# melzi.net
KiCad netlist of a schematic drawn in EAGLE
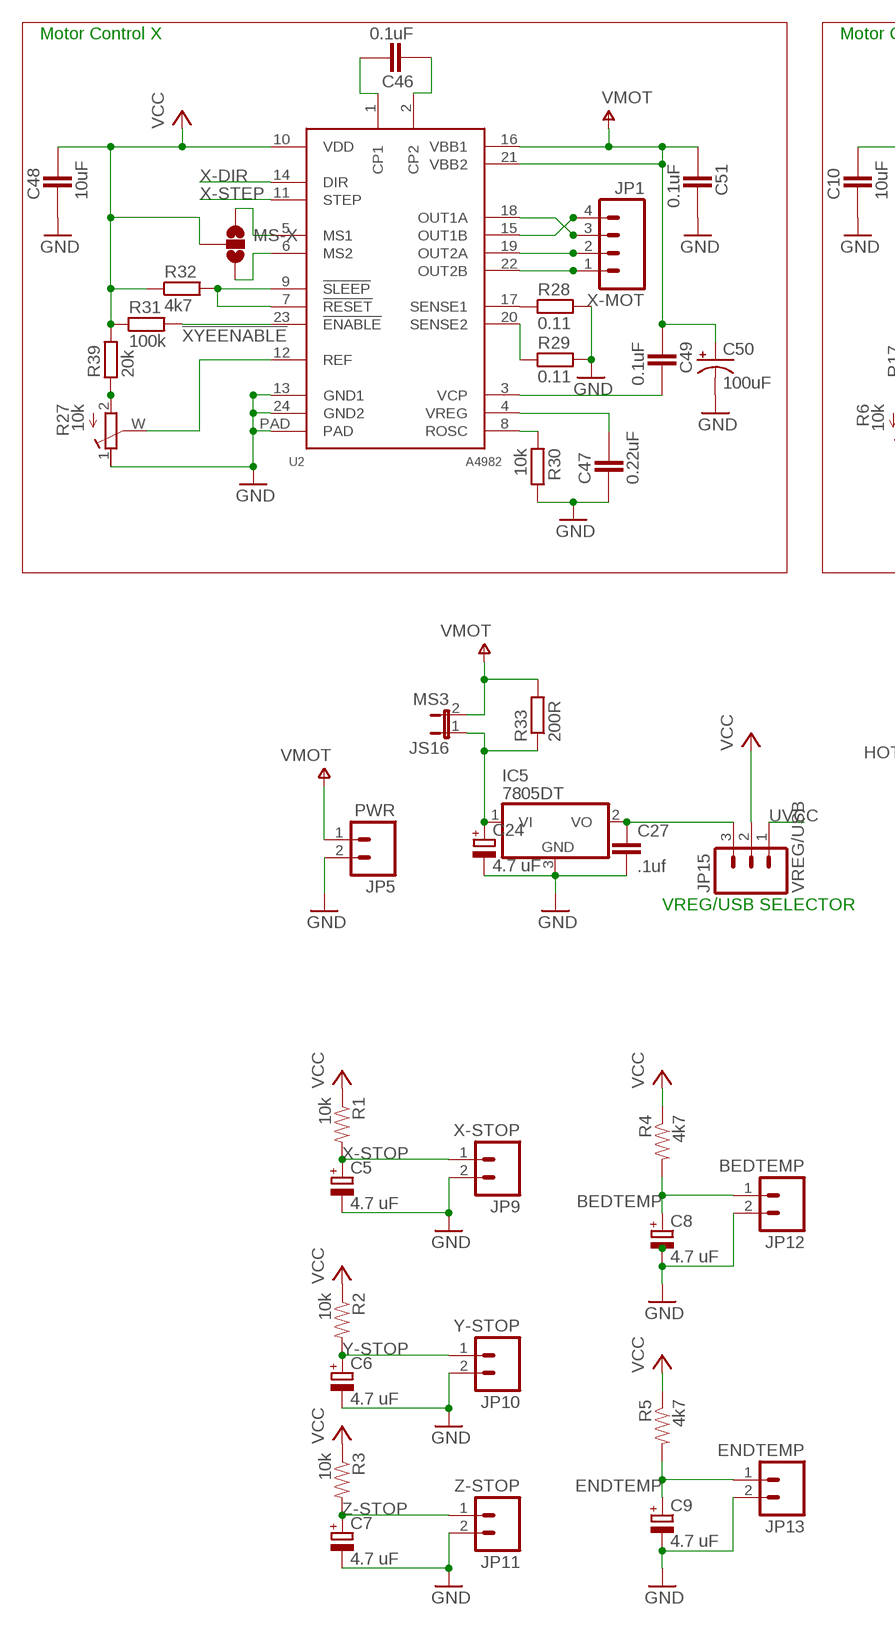
[diagram p0: schematic, sheet 1, part 1 of 2]
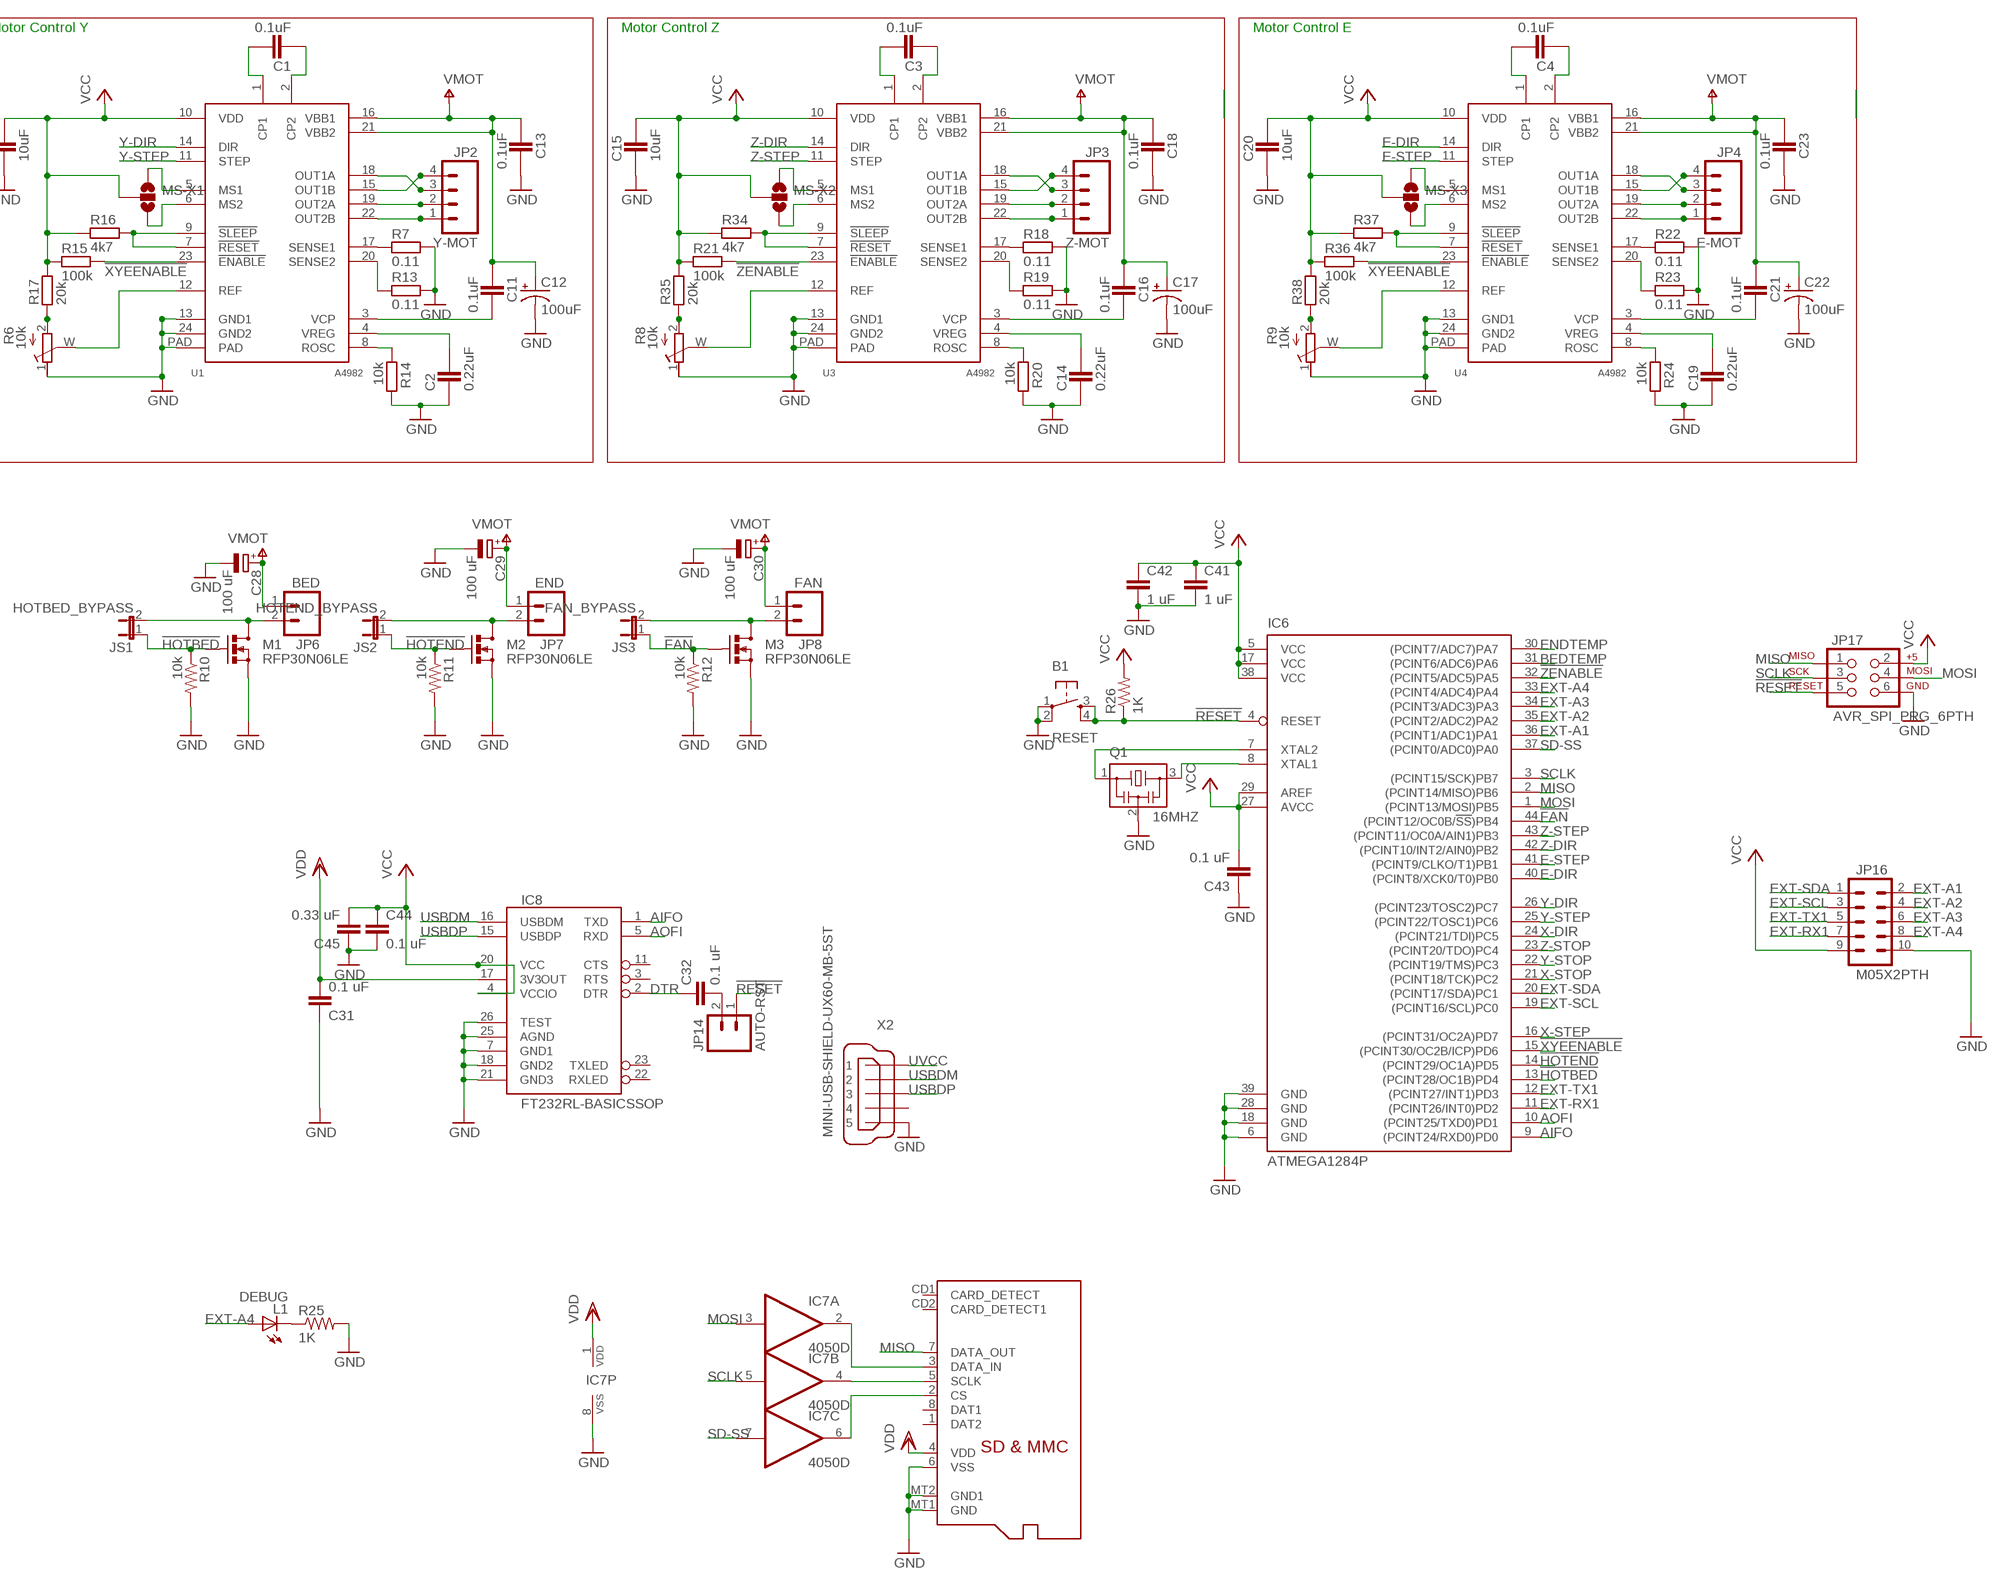
[diagram p1: schematic, sheet 1, part 2 of 2]

(export (version "E")
  (design (tool "Eeschema 10.0.6"))
  (components
    (comp (ref "B1")
      (value "RESET")
      (footprint "eagle-import:TACTILE_SWITCH_SMD")
      (libsource (lib "eagle-import") (part "TAC_SWITCHSMD"))
    )
    (comp (ref "C1")
      (value "0.1uF")
      (footprint "eagle-import:CAPC2012X145AN")
      (libsource (lib "eagle-import") (part "CAPACITOR_0805"))
    )
    (comp (ref "C2")
      (value "0.22uF")
      (footprint "eagle-import:CAPC2012X145AN")
      (libsource (lib "eagle-import") (part "CAPACITOR_0805"))
    )
    (comp (ref "C3")
      (value "0.1uF")
      (footprint "eagle-import:CAPC2012X145AN")
      (libsource (lib "eagle-import") (part "CAPACITOR_0805"))
    )
    (comp (ref "C4")
      (value "0.1uF")
      (footprint "eagle-import:CAPC2012X145AN")
      (libsource (lib "eagle-import") (part "CAPACITOR_0805"))
    )
    (comp (ref "C5")
      (value "4.7 uF")
      (footprint "eagle-import:SMC_C")
      (libsource (lib "eagle-import") (part "CPOL-EUSMCC"))
    )
    (comp (ref "C6")
      (value "4.7 uF")
      (footprint "eagle-import:SMC_C")
      (libsource (lib "eagle-import") (part "CPOL-EUSMCC"))
    )
    (comp (ref "C7")
      (value "4.7 uF")
      (footprint "eagle-import:SMC_C")
      (libsource (lib "eagle-import") (part "CPOL-EUSMCC"))
    )
    (comp (ref "C8")
      (value "4.7 uF")
      (footprint "eagle-import:SMC_C")
      (libsource (lib "eagle-import") (part "CPOL-EUSMCC"))
    )
    (comp (ref "C9")
      (value "4.7 uF")
      (footprint "eagle-import:SMC_C")
      (libsource (lib "eagle-import") (part "CPOL-EUSMCC"))
    )
    (comp (ref "C10")
      (value "10uF")
      (footprint "eagle-import:CAPC2012X145AN")
      (libsource (lib "eagle-import") (part "CAPACITOR_0805"))
    )
    (comp (ref "C11")
      (value "0.1uF")
      (footprint "eagle-import:CAPC2012X145AN")
      (libsource (lib "eagle-import") (part "CAPACITOR_0805"))
    )
    (comp (ref "C12")
      (value "100uF")
      (footprint "eagle-import:PANASONIC_D")
      (libsource (lib "eagle-import") (part "CPOL-USD"))
    )
    (comp (ref "C13")
      (value "0.1uF")
      (footprint "eagle-import:CAPC2012X145AN")
      (libsource (lib "eagle-import") (part "CAPACITOR_0805"))
    )
    (comp (ref "C14")
      (value "0.22uF")
      (footprint "eagle-import:CAPC2012X145AN")
      (libsource (lib "eagle-import") (part "CAPACITOR_0805"))
    )
    (comp (ref "C15")
      (value "10uF")
      (footprint "eagle-import:CAPC2012X145AN")
      (libsource (lib "eagle-import") (part "CAPACITOR_0805"))
    )
    (comp (ref "C16")
      (value "0.1uF")
      (footprint "eagle-import:CAPC2012X145AN")
      (libsource (lib "eagle-import") (part "CAPACITOR_0805"))
    )
    (comp (ref "C17")
      (value "100uF")
      (footprint "eagle-import:PANASONIC_D")
      (libsource (lib "eagle-import") (part "CPOL-USD"))
    )
    (comp (ref "C18")
      (value "0.1uF")
      (footprint "eagle-import:CAPC2012X145AN")
      (libsource (lib "eagle-import") (part "CAPACITOR_0805"))
    )
    (comp (ref "C19")
      (value "0.22uF")
      (footprint "eagle-import:CAPC2012X145AN")
      (libsource (lib "eagle-import") (part "CAPACITOR_0805"))
    )
    (comp (ref "C20")
      (value "10uF")
      (footprint "eagle-import:CAPC2012X145AN")
      (libsource (lib "eagle-import") (part "CAPACITOR_0805"))
    )
    (comp (ref "C21")
      (value "0.1uF")
      (footprint "eagle-import:CAPC2012X145AN")
      (libsource (lib "eagle-import") (part "CAPACITOR_0805"))
    )
    (comp (ref "C22")
      (value "100uF")
      (footprint "eagle-import:PANASONIC_D")
      (libsource (lib "eagle-import") (part "CPOL-USD"))
    )
    (comp (ref "C23")
      (value "0.1uF")
      (footprint "eagle-import:CAPC2012X145AN")
      (libsource (lib "eagle-import") (part "CAPACITOR_0805"))
    )
    (comp (ref "C24")
      (value "4.7 uF")
      (footprint "eagle-import:SMC_C")
      (libsource (lib "eagle-import") (part "CPOL-EUSMCC"))
    )
    (comp (ref "C27")
      (value ".1uf")
      (footprint "eagle-import:0805")
      (libsource (lib "eagle-import") (part "CAP0805"))
    )
    (comp (ref "C28")
      (value "100 uF")
      (footprint "eagle-import:UD-6,3X7,7_NICHICON")
      (libsource (lib "eagle-import") (part "CPOL-EUUD-6,3X7,7"))
    )
    (comp (ref "C29")
      (value "100 uF")
      (footprint "eagle-import:UD-6,3X7,7_NICHICON")
      (libsource (lib "eagle-import") (part "CPOL-EUUD-6,3X7,7"))
    )
    (comp (ref "C30")
      (value "100 uF")
      (footprint "eagle-import:UD-6,3X7,7_NICHICON")
      (libsource (lib "eagle-import") (part "CPOL-EUUD-6,3X7,7"))
    )
    (comp (ref "C31")
      (value "0.1 uF")
      (footprint "eagle-import:C1206")
      (libsource (lib "eagle-import") (part "C-EUC1206"))
    )
    (comp (ref "C32")
      (value "0.1 uF")
      (footprint "eagle-import:C1206")
      (libsource (lib "eagle-import") (part "C-EUC1206"))
    )
    (comp (ref "C41")
      (value "1 uF")
      (footprint "eagle-import:C1206")
      (libsource (lib "eagle-import") (part "C-EUC1206"))
    )
    (comp (ref "C42")
      (value "1 uF")
      (footprint "eagle-import:C1206")
      (libsource (lib "eagle-import") (part "C-EUC1206"))
    )
    (comp (ref "C43")
      (value "0.1 uF")
      (footprint "eagle-import:C1206")
      (libsource (lib "eagle-import") (part "C-EUC1206"))
    )
    (comp (ref "C44")
      (value "0.1 uF")
      (footprint "eagle-import:C1206")
      (libsource (lib "eagle-import") (part "C-EUC1206"))
    )
    (comp (ref "C45")
      (value "0.33 uF")
      (footprint "eagle-import:C1206")
      (libsource (lib "eagle-import") (part "C-EUC1206"))
    )
    (comp (ref "C46")
      (value "0.1uF")
      (footprint "eagle-import:CAPC2012X145AN")
      (libsource (lib "eagle-import") (part "CAPACITOR_0805"))
    )
    (comp (ref "C47")
      (value "0.22uF")
      (footprint "eagle-import:CAPC2012X145AN")
      (libsource (lib "eagle-import") (part "CAPACITOR_0805"))
    )
    (comp (ref "C48")
      (value "10uF")
      (footprint "eagle-import:CAPC2012X145AN")
      (libsource (lib "eagle-import") (part "CAPACITOR_0805"))
    )
    (comp (ref "C49")
      (value "0.1uF")
      (footprint "eagle-import:CAPC2012X145AN")
      (libsource (lib "eagle-import") (part "CAPACITOR_0805"))
    )
    (comp (ref "C50")
      (value "100uF")
      (footprint "eagle-import:PANASONIC_D")
      (libsource (lib "eagle-import") (part "CPOL-USD"))
    )
    (comp (ref "C51")
      (value "0.1uF")
      (footprint "eagle-import:CAPC2012X145AN")
      (libsource (lib "eagle-import") (part "CAPACITOR_0805"))
    )
    (comp (ref "IC5")
      (value "7805DT")
      (footprint "eagle-import:TO252")
      (libsource (lib "eagle-import") (part "78DT05"))
    )
    (comp (ref "IC6")
      (value "ATMEGA1284P")
      (footprint "eagle-import:TQFP44")
      (fields (field (name "MPN") "ATMEGA644PV-10AU"))
      (libsource (lib "eagle-import") (part "ATMEGA644A"))
    )
    (comp (ref "IC7")
      (value "4050D")
      (footprint "eagle-import:SO16")
      (libsource (lib "eagle-import") (part "4050D"))
    )
    (comp (ref "IC8")
      (value "FT232RL-BASICSSOP")
      (footprint "eagle-import:SSOP28DB")
      (libsource (lib "eagle-import") (part "FT232RL-BASICSSOP"))
    )
    (comp (ref "JP1")
      (value "X-MOT")
      (footprint "eagle-import:SCREWTERMINAL-3.5MM-4")
      (libsource (lib "eagle-import") (part "M04SCREW"))
    )
    (comp (ref "JP2")
      (value "Y-MOT")
      (footprint "eagle-import:SCREWTERMINAL-3.5MM-4")
      (libsource (lib "eagle-import") (part "M04SCREW"))
    )
    (comp (ref "JP3")
      (value "Z-MOT")
      (footprint "eagle-import:SCREWTERMINAL-3.5MM-4")
      (libsource (lib "eagle-import") (part "M04SCREW"))
    )
    (comp (ref "JP4")
      (value "E-MOT")
      (footprint "eagle-import:SCREWTERMINAL-3.5MM-4")
      (libsource (lib "eagle-import") (part "M04SCREW"))
    )
    (comp (ref "JP5")
      (value "PWR")
      (footprint "eagle-import:SCREWTERMINAL-5MM-2")
      (libsource (lib "eagle-import") (part "M025MM"))
    )
    (comp (ref "JP6")
      (value "BED")
      (footprint "eagle-import:SCREWTERMINAL-5MM-2")
      (libsource (lib "eagle-import") (part "M025MM"))
    )
    (comp (ref "JP7")
      (value "END")
      (footprint "eagle-import:SCREWTERMINAL-5MM-2")
      (libsource (lib "eagle-import") (part "M025MM"))
    )
    (comp (ref "JP8")
      (value "FAN")
      (footprint "eagle-import:SCREWTERMINAL-5MM-2")
      (libsource (lib "eagle-import") (part "M025MM"))
    )
    (comp (ref "JP9")
      (value "X-STOP")
      (footprint "eagle-import:SCREWTERMINAL-3.5MM-2")
      (libsource (lib "eagle-import") (part "M023.5MM"))
    )
    (comp (ref "JP10")
      (value "Y-STOP")
      (footprint "eagle-import:SCREWTERMINAL-3.5MM-2")
      (libsource (lib "eagle-import") (part "M023.5MM"))
    )
    (comp (ref "JP11")
      (value "Z-STOP")
      (footprint "eagle-import:SCREWTERMINAL-3.5MM-2")
      (libsource (lib "eagle-import") (part "M023.5MM"))
    )
    (comp (ref "JP12")
      (value "BEDTEMP")
      (footprint "eagle-import:SCREWTERMINAL-3.5MM-2")
      (libsource (lib "eagle-import") (part "M023.5MM"))
    )
    (comp (ref "JP13")
      (value "ENDTEMP")
      (footprint "eagle-import:SCREWTERMINAL-3.5MM-2")
      (libsource (lib "eagle-import") (part "M023.5MM"))
    )
    (comp (ref "JP14")
      (value "AUTO-RST")
      (footprint "eagle-import:1X02")
      (libsource (lib "eagle-import") (part "M02PTH"))
    )
    (comp (ref "JP15")
      (value "VREG/USB")
      (footprint "eagle-import:1X03")
      (libsource (lib "eagle-import") (part "M03PTH"))
    )
    (comp (ref "JP16")
      (value "M05X2PTH")
      (footprint "eagle-import:AVR_ICSP")
      (libsource (lib "eagle-import") (part "M05X2PTH"))
    )
    (comp (ref "JP17")
      (value "AVR_SPI_PRG_6PTH")
      (footprint "eagle-import:2X3")
      (libsource (lib "eagle-import") (part "AVR_SPI_PRG_6PTH"))
    )
    (comp (ref "JS1")
      (value "HOTBED_BYPASS")
      (footprint "eagle-import:SJ_2S-NO")
      (libsource (lib "eagle-import") (part "JUMPER-2SMD-NO"))
    )
    (comp (ref "JS2")
      (value "HOTEND_BYPASS")
      (footprint "eagle-import:SJ_2S-NO")
      (libsource (lib "eagle-import") (part "JUMPER-2SMD-NO"))
    )
    (comp (ref "JS3")
      (value "FAN_BYPASS")
      (footprint "eagle-import:SJ_2S-NO")
      (libsource (lib "eagle-import") (part "JUMPER-2SMD-NO"))
    )
    (comp (ref "JS16")
      (value "MS3")
      (footprint "eagle-import:SJ_2S")
      (libsource (lib "eagle-import") (part "JUMPER-2SMD-NC"))
    )
    (comp (ref "L1")
      (value "DEBUG")
      (footprint "eagle-import:LED-1206")
      (libsource (lib "eagle-import") (part "LED1206"))
    )
    (comp (ref "M1")
      (value "RFP30N06LE")
      (footprint "eagle-import:DPAK")
      (libsource (lib "eagle-import") (part "MOSFET-NCHANNELFDD8580"))
    )
    (comp (ref "M2")
      (value "RFP30N06LE")
      (footprint "eagle-import:DPAK")
      (libsource (lib "eagle-import") (part "MOSFET-NCHANNELFDD8580"))
    )
    (comp (ref "M3")
      (value "RFP30N06LE")
      (footprint "eagle-import:DPAK")
      (libsource (lib "eagle-import") (part "MOSFET-NCHANNELFDD8580"))
    )
    (comp (ref "MS-X")
      (value "SOLDERJUMPER_2WAYCONNECTED")
      (footprint "eagle-import:SJ_3_CONNECTED")
      (libsource (lib "eagle-import") (part "SOLDERJUMPER_2WAYCONNECTED"))
    )
    (comp (ref "MS-X1")
      (value "SOLDERJUMPER_2WAYCONNECTED")
      (footprint "eagle-import:SJ_3_CONNECTED")
      (libsource (lib "eagle-import") (part "SOLDERJUMPER_2WAYCONNECTED"))
    )
    (comp (ref "MS-X2")
      (value "SOLDERJUMPER_2WAYCONNECTED")
      (footprint "eagle-import:SJ_3_CONNECTED")
      (libsource (lib "eagle-import") (part "SOLDERJUMPER_2WAYCONNECTED"))
    )
    (comp (ref "MS-X3")
      (value "SOLDERJUMPER_2WAYCONNECTED")
      (footprint "eagle-import:SJ_3_CONNECTED")
      (libsource (lib "eagle-import") (part "SOLDERJUMPER_2WAYCONNECTED"))
    )
    (comp (ref "Q1")
      (value "16MHZ")
      (footprint "eagle-import:CSTCR6M")
      (fields (field (name "MPN") "CSTCR6M00G53-R0"))
      (libsource (lib "eagle-import") (part "CSTCR6M00G53Z"))
    )
    (comp (ref "R1")
      (value "10k")
      (footprint "eagle-import:1206")
      (libsource (lib "eagle-import") (part "RESISTOR1206"))
    )
    (comp (ref "R2")
      (value "10k")
      (footprint "eagle-import:1206")
      (libsource (lib "eagle-import") (part "RESISTOR1206"))
    )
    (comp (ref "R3")
      (value "10k")
      (footprint "eagle-import:1206")
      (libsource (lib "eagle-import") (part "RESISTOR1206"))
    )
    (comp (ref "R4")
      (value "4k7")
      (footprint "eagle-import:1206")
      (libsource (lib "eagle-import") (part "RESISTOR1206"))
    )
    (comp (ref "R5")
      (value "4k7")
      (footprint "eagle-import:1206")
      (libsource (lib "eagle-import") (part "RESISTOR1206"))
    )
    (comp (ref "R6")
      (value "10k")
      (footprint "eagle-import:RTRIM-ST4ETB")
      (libsource (lib "eagle-import") (part "RTRIM-ST-4EA"))
    )
    (comp (ref "R7")
      (value "0.11")
      (footprint "eagle-import:RESC2012X70N")
      (libsource (lib "eagle-import") (part "RESISTOR_0805"))
    )
    (comp (ref "R8")
      (value "10k")
      (footprint "eagle-import:RTRIM-ST4ETB")
      (libsource (lib "eagle-import") (part "RTRIM-ST-4EA"))
    )
    (comp (ref "R9")
      (value "10k")
      (footprint "eagle-import:RTRIM-ST4ETB")
      (libsource (lib "eagle-import") (part "RTRIM-ST-4EA"))
    )
    (comp (ref "R10")
      (value "10k")
      (footprint "eagle-import:1206")
      (libsource (lib "eagle-import") (part "RESISTOR1206"))
    )
    (comp (ref "R11")
      (value "10k")
      (footprint "eagle-import:1206")
      (libsource (lib "eagle-import") (part "RESISTOR1206"))
    )
    (comp (ref "R12")
      (value "10k")
      (footprint "eagle-import:1206")
      (libsource (lib "eagle-import") (part "RESISTOR1206"))
    )
    (comp (ref "R13")
      (value "0.11")
      (footprint "eagle-import:RESC2012X70N")
      (libsource (lib "eagle-import") (part "RESISTOR_0805"))
    )
    (comp (ref "R14")
      (value "10k")
      (footprint "eagle-import:RESC2012X70N")
      (libsource (lib "eagle-import") (part "RESISTOR_0805"))
    )
    (comp (ref "R15")
      (value "100k")
      (footprint "eagle-import:RESC2012X70N")
      (libsource (lib "eagle-import") (part "RESISTOR_0805"))
    )
    (comp (ref "R16")
      (value "4k7")
      (footprint "eagle-import:RESC2012X70N")
      (libsource (lib "eagle-import") (part "RESISTOR_0805"))
    )
    (comp (ref "R17")
      (value "20k")
      (footprint "eagle-import:RESC2012X70N")
      (libsource (lib "eagle-import") (part "RESISTOR_0805"))
    )
    (comp (ref "R18")
      (value "0.11")
      (footprint "eagle-import:RESC2012X70N")
      (libsource (lib "eagle-import") (part "RESISTOR_0805"))
    )
    (comp (ref "R19")
      (value "0.11")
      (footprint "eagle-import:RESC2012X70N")
      (libsource (lib "eagle-import") (part "RESISTOR_0805"))
    )
    (comp (ref "R20")
      (value "10k")
      (footprint "eagle-import:RESC2012X70N")
      (libsource (lib "eagle-import") (part "RESISTOR_0805"))
    )
    (comp (ref "R21")
      (value "100k")
      (footprint "eagle-import:RESC2012X70N")
      (libsource (lib "eagle-import") (part "RESISTOR_0805"))
    )
    (comp (ref "R22")
      (value "0.11")
      (footprint "eagle-import:RESC2012X70N")
      (libsource (lib "eagle-import") (part "RESISTOR_0805"))
    )
    (comp (ref "R23")
      (value "0.11")
      (footprint "eagle-import:RESC2012X70N")
      (libsource (lib "eagle-import") (part "RESISTOR_0805"))
    )
    (comp (ref "R24")
      (value "10k")
      (footprint "eagle-import:RESC2012X70N")
      (libsource (lib "eagle-import") (part "RESISTOR_0805"))
    )
    (comp (ref "R25")
      (value "1K")
      (footprint "eagle-import:1206")
      (libsource (lib "eagle-import") (part "RESISTOR1206"))
    )
    (comp (ref "R26")
      (value "1K")
      (footprint "eagle-import:1206")
      (libsource (lib "eagle-import") (part "RESISTOR1206"))
    )
    (comp (ref "R27")
      (value "10k")
      (footprint "eagle-import:RTRIM-ST4ETB")
      (libsource (lib "eagle-import") (part "RTRIM-ST-4EA"))
    )
    (comp (ref "R28")
      (value "0.11")
      (footprint "eagle-import:RESC2012X70N")
      (libsource (lib "eagle-import") (part "RESISTOR_0805"))
    )
    (comp (ref "R29")
      (value "0.11")
      (footprint "eagle-import:RESC2012X70N")
      (libsource (lib "eagle-import") (part "RESISTOR_0805"))
    )
    (comp (ref "R30")
      (value "10k")
      (footprint "eagle-import:RESC2012X70N")
      (libsource (lib "eagle-import") (part "RESISTOR_0805"))
    )
    (comp (ref "R31")
      (value "100k")
      (footprint "eagle-import:RESC2012X70N")
      (libsource (lib "eagle-import") (part "RESISTOR_0805"))
    )
    (comp (ref "R32")
      (value "4k7")
      (footprint "eagle-import:RESC2012X70N")
      (libsource (lib "eagle-import") (part "RESISTOR_0805"))
    )
    (comp (ref "R33")
      (value "200R")
      (footprint "eagle-import:0309V")
      (libsource (lib "eagle-import") (part "R-EU_0309/V"))
    )
    (comp (ref "R34")
      (value "4k7")
      (footprint "eagle-import:RESC2012X70N")
      (libsource (lib "eagle-import") (part "RESISTOR_0805"))
    )
    (comp (ref "R35")
      (value "20k")
      (footprint "eagle-import:RESC2012X70N")
      (libsource (lib "eagle-import") (part "RESISTOR_0805"))
    )
    (comp (ref "R36")
      (value "100k")
      (footprint "eagle-import:RESC2012X70N")
      (libsource (lib "eagle-import") (part "RESISTOR_0805"))
    )
    (comp (ref "R37")
      (value "4k7")
      (footprint "eagle-import:RESC2012X70N")
      (libsource (lib "eagle-import") (part "RESISTOR_0805"))
    )
    (comp (ref "R38")
      (value "20k")
      (footprint "eagle-import:RESC2012X70N")
      (libsource (lib "eagle-import") (part "RESISTOR_0805"))
    )
    (comp (ref "R39")
      (value "20k")
      (footprint "eagle-import:RESC2012X70N")
      (libsource (lib "eagle-import") (part "RESISTOR_0805"))
    )
    (comp (ref "U1")
      (value "A4982")
      (footprint "eagle-import:TSSOP-24")
      (libsource (lib "eagle-import") (part "A4982"))
    )
    (comp (ref "U2")
      (value "A4982")
      (footprint "eagle-import:TSSOP-24")
      (libsource (lib "eagle-import") (part "A4982"))
    )
    (comp (ref "U3")
      (value "A4982")
      (footprint "eagle-import:TSSOP-24")
      (libsource (lib "eagle-import") (part "A4982"))
    )
    (comp (ref "U4")
      (value "A4982")
      (footprint "eagle-import:TSSOP-24")
      (libsource (lib "eagle-import") (part "A4982"))
    )
    (comp (ref "X1")
      (value "MICROSD")
      (footprint "eagle-import:MICROSD")
      (libsource (lib "eagle-import") (part "MICROSD"))
    )
    (comp (ref "X2")
      (value "MINI-USB-SHIELD-UX60-MB-5ST")
      (footprint "eagle-import:UX60-MB-5ST")
      (libsource (lib "eagle-import") (part "MINI-USB-SHIELD-UX60-MB-5ST"))
    )
  )
  (nets
    (net (code "1") (name "/AIFO") (class "Default")
      (node (ref "IC6") (pin "9") (pinfunction "(PCINT24/RXD0)PD0_9") (pintype "bidirectional"))
      (node (ref "IC8") (pin "1") (pinfunction "TXD_1") (pintype "output"))
    )
    (net (code "2") (name "/AOFI") (class "Default")
      (node (ref "IC6") (pin "10") (pinfunction "(PCINT25/TXD0)PD1_10") (pintype "bidirectional"))
      (node (ref "IC8") (pin "5") (pinfunction "RXD_5") (pintype "input"))
    )
    (net (code "3") (name "/BEDTEMP") (class "Default")
      (node (ref "C8") (pin "+") (pinfunction "+_+") (pintype "passive"))
      (node (ref "IC6") (pin "31") (pinfunction "(PCINT6/ADC6)PA6_31") (pintype "bidirectional"))
      (node (ref "JP12") (pin "1") (pinfunction "1_1") (pintype "passive"))
      (node (ref "R4") (pin "2") (pinfunction "2_2") (pintype "passive"))
    )
    (net (code "4") (name "/DTR") (class "Default")
      (node (ref "C32") (pin "1") (pinfunction "1_1") (pintype "passive"))
      (node (ref "IC8") (pin "2") (pinfunction "DTR_2") (pintype "bidirectional"))
    )
    (net (code "5") (name "/E-DIR") (class "Default")
      (node (ref "IC6") (pin "40") (pinfunction "(PCINT8/XCK0/T0)PB0_40") (pintype "bidirectional"))
      (node (ref "U4") (pin "14") (pinfunction "DIR_14") (pintype "input"))
    )
    (net (code "6") (name "/E-STEP") (class "Default")
      (node (ref "IC6") (pin "41") (pinfunction "(PCINT9/CLKO/T1)PB1_41") (pintype "bidirectional"))
      (node (ref "U4") (pin "11") (pinfunction "STEP_11") (pintype "input"))
    )
    (net (code "7") (name "/ENDTEMP") (class "Default")
      (node (ref "C9") (pin "+") (pinfunction "+_+") (pintype "passive"))
      (node (ref "IC6") (pin "30") (pinfunction "(PCINT7/ADC7)PA7_30") (pintype "bidirectional"))
      (node (ref "JP13") (pin "1") (pinfunction "1_1") (pintype "passive"))
      (node (ref "R5") (pin "2") (pinfunction "2_2") (pintype "passive"))
    )
    (net (code "8") (name "/EXT-A1") (class "Default")
      (node (ref "IC6") (pin "36") (pinfunction "(PCINT1/ADC1)PA1_36") (pintype "bidirectional"))
      (node (ref "JP16") (pin "2") (pinfunction "2_2") (pintype "passive"))
    )
    (net (code "9") (name "/EXT-A2") (class "Default")
      (node (ref "IC6") (pin "35") (pinfunction "(PCINT2/ADC2)PA2_35") (pintype "bidirectional"))
      (node (ref "JP16") (pin "4") (pinfunction "4_4") (pintype "passive"))
    )
    (net (code "10") (name "/EXT-A3") (class "Default")
      (node (ref "IC6") (pin "34") (pinfunction "(PCINT3/ADC3)PA3_34") (pintype "bidirectional"))
      (node (ref "JP16") (pin "6") (pinfunction "6_6") (pintype "passive"))
    )
    (net (code "11") (name "/EXT-A4") (class "Default")
      (node (ref "IC6") (pin "33") (pinfunction "(PCINT4/ADC4)PA4_33") (pintype "bidirectional"))
      (node (ref "JP16") (pin "8") (pinfunction "8_8") (pintype "passive"))
      (node (ref "L1") (pin "A") (pinfunction "A_A") (pintype "passive"))
    )
    (net (code "12") (name "/EXT-RX1") (class "Default")
      (node (ref "IC6") (pin "11") (pinfunction "(PCINT26/INT0)PD2_11") (pintype "bidirectional"))
      (node (ref "JP16") (pin "7") (pinfunction "7_7") (pintype "passive"))
    )
    (net (code "13") (name "/EXT-SCL") (class "Default")
      (node (ref "IC6") (pin "19") (pinfunction "(PCINT16/SCL)PC0_19") (pintype "output"))
      (node (ref "JP16") (pin "3") (pinfunction "3_3") (pintype "passive"))
    )
    (net (code "14") (name "/EXT-SDA") (class "Default")
      (node (ref "IC6") (pin "20") (pinfunction "(PCINT17/SDA)PC1_20") (pintype "output"))
      (node (ref "JP16") (pin "1") (pinfunction "1_1") (pintype "passive"))
    )
    (net (code "15") (name "/EXT-TX1") (class "Default")
      (node (ref "IC6") (pin "12") (pinfunction "(PCINT27/INT1)PD3_12") (pintype "bidirectional"))
      (node (ref "JP16") (pin "5") (pinfunction "5_5") (pintype "passive"))
    )
    (net (code "16") (name "/MISO") (class "Default")
      (node (ref "IC6") (pin "2") (pinfunction "(PCINT14/MISO)PB6_2") (pintype "bidirectional"))
      (node (ref "JP17") (pin "1") (pinfunction "1_1") (pintype "passive"))
      (node (ref "X1") (pin "7") (pinfunction "DATA_OUT_7") (pintype "output"))
    )
    (net (code "17") (name "/MOSI") (class "Default")
      (node (ref "IC6") (pin "1") (pinfunction "(PCINT13/MOSI)PB5_1") (pintype "bidirectional"))
      (node (ref "IC7") (pin "3") (pinfunction "I_3") (pintype "input"))
      (node (ref "JP17") (pin "4") (pinfunction "4_4") (pintype "passive"))
    )
    (net (code "18") (name "/SCLK") (class "Default")
      (node (ref "IC6") (pin "3") (pinfunction "(PCINT15/SCK)PB7_3") (pintype "bidirectional"))
      (node (ref "IC7") (pin "5") (pinfunction "I_5") (pintype "input"))
      (node (ref "JP17") (pin "3") (pinfunction "3_3") (pintype "passive"))
    )
    (net (code "19") (name "/SD-SS") (class "Default")
      (node (ref "IC6") (pin "37") (pinfunction "(PCINT0/ADC0)PA0_37") (pintype "bidirectional"))
      (node (ref "IC7") (pin "7") (pinfunction "I_7") (pintype "input"))
    )
    (net (code "20") (name "/USBDM") (class "Default")
      (node (ref "IC8") (pin "16") (pinfunction "USBDM_16") (pintype "bidirectional"))
      (node (ref "X2") (pin "2") (pinfunction "2_2") (pintype "input"))
    )
    (net (code "21") (name "/USBDP") (class "Default")
      (node (ref "IC8") (pin "15") (pinfunction "USBDP_15") (pintype "bidirectional"))
      (node (ref "X2") (pin "3") (pinfunction "3_3") (pintype "input"))
    )
    (net (code "22") (name "/UVCC") (class "Default")
      (node (ref "JP15") (pin "1") (pinfunction "1_1") (pintype "passive"))
      (node (ref "X2") (pin "1") (pinfunction "1_1") (pintype "input"))
    )
    (net (code "23") (name "/X-DIR") (class "Default")
      (node (ref "IC6") (pin "24") (pinfunction "(PCINT21/TDI)PC5_24") (pintype "output"))
      (node (ref "U2") (pin "14") (pinfunction "DIR_14") (pintype "input"))
    )
    (net (code "24") (name "/X-STEP") (class "Default")
      (node (ref "IC6") (pin "16") (pinfunction "(PCINT31/OC2A)PD7_16") (pintype "bidirectional"))
      (node (ref "U2") (pin "11") (pinfunction "STEP_11") (pintype "input"))
    )
    (net (code "25") (name "/X-STOP") (class "Default")
      (node (ref "C5") (pin "+") (pinfunction "+_+") (pintype "passive"))
      (node (ref "IC6") (pin "21") (pinfunction "(PCINT18/TCK)PC2_21") (pintype "output"))
      (node (ref "JP9") (pin "1") (pinfunction "1_1") (pintype "passive"))
      (node (ref "R1") (pin "2") (pinfunction "2_2") (pintype "passive"))
    )
    (net (code "26") (name "/Y-DIR") (class "Default")
      (node (ref "IC6") (pin "26") (pinfunction "(PCINT23/TOSC2)PC7_26") (pintype "output"))
      (node (ref "U1") (pin "14") (pinfunction "DIR_14") (pintype "input"))
    )
    (net (code "27") (name "/Y-STEP") (class "Default")
      (node (ref "IC6") (pin "25") (pinfunction "(PCINT22/TOSC1)PC6_25") (pintype "output"))
      (node (ref "U1") (pin "11") (pinfunction "STEP_11") (pintype "input"))
    )
    (net (code "28") (name "/Y-STOP") (class "Default")
      (node (ref "C6") (pin "+") (pinfunction "+_+") (pintype "passive"))
      (node (ref "IC6") (pin "22") (pinfunction "(PCINT19/TMS)PC3_22") (pintype "output"))
      (node (ref "JP10") (pin "1") (pinfunction "1_1") (pintype "passive"))
      (node (ref "R2") (pin "2") (pinfunction "2_2") (pintype "passive"))
    )
    (net (code "29") (name "/Z-DIR") (class "Default")
      (node (ref "IC6") (pin "42") (pinfunction "(PCINT10/INT2/AIN0)PB2_42") (pintype "bidirectional"))
      (node (ref "U3") (pin "14") (pinfunction "DIR_14") (pintype "input"))
    )
    (net (code "30") (name "/Z-STEP") (class "Default")
      (node (ref "IC6") (pin "43") (pinfunction "(PCINT11/OC0A/AIN1)PB3_43") (pintype "bidirectional"))
      (node (ref "U3") (pin "11") (pinfunction "STEP_11") (pintype "input"))
    )
    (net (code "31") (name "/Z-STOP") (class "Default")
      (node (ref "C7") (pin "+") (pinfunction "+_+") (pintype "passive"))
      (node (ref "IC6") (pin "23") (pinfunction "(PCINT20/TDO)PC4_23") (pintype "output"))
      (node (ref "JP11") (pin "1") (pinfunction "1_1") (pintype "passive"))
      (node (ref "R3") (pin "2") (pinfunction "2_2") (pintype "passive"))
    )
    (net (code "32") (name "/~{FAN}") (class "Default")
      (node (ref "IC6") (pin "44") (pinfunction "(PCINT12/OC0B/~{SS})PB4_44") (pintype "bidirectional"))
      (node (ref "JS3") (pin "1") (pinfunction "1_1") (pintype "passive"))
      (node (ref "M3") (pin "1") (pinfunction "G_1") (pintype "passive"))
      (node (ref "R12") (pin "1") (pinfunction "1_1") (pintype "passive"))
    )
    (net (code "33") (name "/~{HOTBED}") (class "Default")
      (node (ref "IC6") (pin "13") (pinfunction "(PCINT28/OC1B)PD4_13") (pintype "bidirectional"))
      (node (ref "JS1") (pin "1") (pinfunction "1_1") (pintype "passive"))
      (node (ref "M1") (pin "1") (pinfunction "G_1") (pintype "passive"))
      (node (ref "R10") (pin "1") (pinfunction "1_1") (pintype "passive"))
    )
    (net (code "34") (name "/~{HOTEND}") (class "Default")
      (node (ref "IC6") (pin "14") (pinfunction "(PCINT29/OC1A)PD5_14") (pintype "bidirectional"))
      (node (ref "JS2") (pin "1") (pinfunction "1_1") (pintype "passive"))
      (node (ref "M2") (pin "1") (pinfunction "G_1") (pintype "passive"))
      (node (ref "R11") (pin "1") (pinfunction "1_1") (pintype "passive"))
    )
    (net (code "35") (name "/~{RESET}") (class "Default")
      (node (ref "B1") (pin "3") (pinfunction "3_3") (pintype "passive"))
      (node (ref "B1") (pin "4") (pinfunction "4_4") (pintype "passive"))
      (node (ref "IC6") (pin "4") (pinfunction "RESET_4") (pintype "input"))
      (node (ref "JP14") (pin "1") (pinfunction "1_1") (pintype "passive"))
      (node (ref "JP17") (pin "5") (pinfunction "5_5") (pintype "passive"))
      (node (ref "R26") (pin "1") (pinfunction "1_1") (pintype "passive"))
    )
    (net (code "36") (name "/~{XYEENABLE}") (class "Default")
      (node (ref "IC6") (pin "15") (pinfunction "(PCINT30/OC2B/ICP)PD6_15") (pintype "bidirectional"))
      (node (ref "R15") (pin "2") (pinfunction "2_2") (pintype "passive"))
      (node (ref "R31") (pin "2") (pinfunction "2_2") (pintype "passive"))
      (node (ref "R36") (pin "2") (pinfunction "2_2") (pintype "passive"))
      (node (ref "U1") (pin "23") (pinfunction "~{ENABLE}_23") (pintype "input"))
      (node (ref "U2") (pin "23") (pinfunction "~{ENABLE}_23") (pintype "input"))
      (node (ref "U4") (pin "23") (pinfunction "~{ENABLE}_23") (pintype "input"))
    )
    (net (code "37") (name "/~{ZENABLE}") (class "Default")
      (node (ref "IC6") (pin "32") (pinfunction "(PCINT5/ADC5)PA5_32") (pintype "bidirectional"))
      (node (ref "R21") (pin "2") (pinfunction "2_2") (pintype "passive"))
      (node (ref "U3") (pin "23") (pinfunction "~{ENABLE}_23") (pintype "input"))
    )
    (net (code "38") (name "GND") (class "Default")
      (node (ref "B1") (pin "1") (pinfunction "1_1") (pintype "passive"))
      (node (ref "B1") (pin "2") (pinfunction "2_2") (pintype "passive"))
      (node (ref "C10") (pin "1") (pinfunction "1_1") (pintype "passive"))
      (node (ref "C12") (pin "-") (pinfunction "-_-") (pintype "passive"))
      (node (ref "C13") (pin "2") (pinfunction "2_2") (pintype "passive"))
      (node (ref "C14") (pin "1") (pinfunction "1_1") (pintype "passive"))
      (node (ref "C15") (pin "1") (pinfunction "1_1") (pintype "passive"))
      (node (ref "C17") (pin "-") (pinfunction "-_-") (pintype "passive"))
      (node (ref "C18") (pin "2") (pinfunction "2_2") (pintype "passive"))
      (node (ref "C19") (pin "1") (pinfunction "1_1") (pintype "passive"))
      (node (ref "C2") (pin "1") (pinfunction "1_1") (pintype "passive"))
      (node (ref "C20") (pin "1") (pinfunction "1_1") (pintype "passive"))
      (node (ref "C22") (pin "-") (pinfunction "-_-") (pintype "passive"))
      (node (ref "C23") (pin "2") (pinfunction "2_2") (pintype "passive"))
      (node (ref "C24") (pin "-") (pinfunction "-_-") (pintype "passive"))
      (node (ref "C27") (pin "2") (pinfunction "2_2") (pintype "passive"))
      (node (ref "C28") (pin "-") (pinfunction "-_-") (pintype "passive"))
      (node (ref "C29") (pin "-") (pinfunction "-_-") (pintype "passive"))
      (node (ref "C30") (pin "-") (pinfunction "-_-") (pintype "passive"))
      (node (ref "C31") (pin "1") (pinfunction "1_1") (pintype "passive"))
      (node (ref "C41") (pin "2") (pinfunction "2_2") (pintype "passive"))
      (node (ref "C42") (pin "2") (pinfunction "2_2") (pintype "passive"))
      (node (ref "C43") (pin "1") (pinfunction "1_1") (pintype "passive"))
      (node (ref "C44") (pin "2") (pinfunction "2_2") (pintype "passive"))
      (node (ref "C45") (pin "1") (pinfunction "1_1") (pintype "passive"))
      (node (ref "C47") (pin "1") (pinfunction "1_1") (pintype "passive"))
      (node (ref "C48") (pin "1") (pinfunction "1_1") (pintype "passive"))
      (node (ref "C5") (pin "-") (pinfunction "-_-") (pintype "passive"))
      (node (ref "C50") (pin "-") (pinfunction "-_-") (pintype "passive"))
      (node (ref "C51") (pin "2") (pinfunction "2_2") (pintype "passive"))
      (node (ref "C6") (pin "-") (pinfunction "-_-") (pintype "passive"))
      (node (ref "C7") (pin "-") (pinfunction "-_-") (pintype "passive"))
      (node (ref "C8") (pin "-") (pinfunction "-_-") (pintype "passive"))
      (node (ref "C9") (pin "-") (pinfunction "-_-") (pintype "passive"))
      (node (ref "IC5") (pin "3") (pinfunction "GND_3") (pintype "passive"))
      (node (ref "IC6") (pin "18") (pinfunction "GND_18") (pintype "power_in"))
      (node (ref "IC6") (pin "28") (pinfunction "GND_28") (pintype "power_in"))
      (node (ref "IC6") (pin "39") (pinfunction "GND_39") (pintype "power_in"))
      (node (ref "IC6") (pin "6") (pinfunction "GND_6") (pintype "power_in"))
      (node (ref "IC7") (pin "8") (pinfunction "VSS_8") (pintype "power_in"))
      (node (ref "IC8") (pin "18") (pinfunction "GND2_18") (pintype "power_in"))
      (node (ref "IC8") (pin "21") (pinfunction "GND3_21") (pintype "power_in"))
      (node (ref "IC8") (pin "25") (pinfunction "AGND_25") (pintype "power_in"))
      (node (ref "IC8") (pin "26") (pinfunction "TEST_26") (pintype "input"))
      (node (ref "IC8") (pin "7") (pinfunction "GND1_7") (pintype "power_in"))
      (node (ref "JP10") (pin "2") (pinfunction "2_2") (pintype "passive"))
      (node (ref "JP11") (pin "2") (pinfunction "2_2") (pintype "passive"))
      (node (ref "JP12") (pin "2") (pinfunction "2_2") (pintype "passive"))
      (node (ref "JP13") (pin "2") (pinfunction "2_2") (pintype "passive"))
      (node (ref "JP16") (pin "10") (pinfunction "10_10") (pintype "passive"))
      (node (ref "JP17") (pin "6") (pinfunction "6_6") (pintype "passive"))
      (node (ref "JP5") (pin "2") (pinfunction "2_2") (pintype "passive"))
      (node (ref "JP9") (pin "2") (pinfunction "2_2") (pintype "passive"))
      (node (ref "M1") (pin "3") (pinfunction "S_3") (pintype "passive"))
      (node (ref "M2") (pin "3") (pinfunction "S_3") (pintype "passive"))
      (node (ref "M3") (pin "3") (pinfunction "S_3") (pintype "passive"))
      (node (ref "Q1") (pin "2") (pinfunction "2_2") (pintype "passive"))
      (node (ref "R10") (pin "2") (pinfunction "2_2") (pintype "passive"))
      (node (ref "R11") (pin "2") (pinfunction "2_2") (pintype "passive"))
      (node (ref "R12") (pin "2") (pinfunction "2_2") (pintype "passive"))
      (node (ref "R13") (pin "2") (pinfunction "2_2") (pintype "passive"))
      (node (ref "R14") (pin "2") (pinfunction "2_2") (pintype "passive"))
      (node (ref "R18") (pin "2") (pinfunction "2_2") (pintype "passive"))
      (node (ref "R19") (pin "2") (pinfunction "2_2") (pintype "passive"))
      (node (ref "R20") (pin "2") (pinfunction "2_2") (pintype "passive"))
      (node (ref "R22") (pin "2") (pinfunction "2_2") (pintype "passive"))
      (node (ref "R23") (pin "2") (pinfunction "2_2") (pintype "passive"))
      (node (ref "R24") (pin "2") (pinfunction "2_2") (pintype "passive"))
      (node (ref "R25") (pin "2") (pinfunction "2_2") (pintype "passive"))
      (node (ref "R27") (pin "1") (pinfunction "A_1") (pintype "passive"))
      (node (ref "R28") (pin "2") (pinfunction "2_2") (pintype "passive"))
      (node (ref "R29") (pin "2") (pinfunction "2_2") (pintype "passive"))
      (node (ref "R30") (pin "2") (pinfunction "2_2") (pintype "passive"))
      (node (ref "R6") (pin "1") (pinfunction "A_1") (pintype "passive"))
      (node (ref "R7") (pin "2") (pinfunction "2_2") (pintype "passive"))
      (node (ref "R8") (pin "1") (pinfunction "A_1") (pintype "passive"))
      (node (ref "R9") (pin "1") (pinfunction "A_1") (pintype "passive"))
      (node (ref "U1") (pin "13") (pinfunction "GND1_13") (pintype "power_in"))
      (node (ref "U1") (pin "24") (pinfunction "GND2_24") (pintype "power_in"))
      (node (ref "U1") (pin "PAD") (pinfunction "PAD_PAD") (pintype "power_in"))
      (node (ref "U2") (pin "13") (pinfunction "GND1_13") (pintype "power_in"))
      (node (ref "U2") (pin "24") (pinfunction "GND2_24") (pintype "power_in"))
      (node (ref "U2") (pin "PAD") (pinfunction "PAD_PAD") (pintype "power_in"))
      (node (ref "U3") (pin "13") (pinfunction "GND1_13") (pintype "power_in"))
      (node (ref "U3") (pin "24") (pinfunction "GND2_24") (pintype "power_in"))
      (node (ref "U3") (pin "PAD") (pinfunction "PAD_PAD") (pintype "power_in"))
      (node (ref "U4") (pin "13") (pinfunction "GND1_13") (pintype "power_in"))
      (node (ref "U4") (pin "24") (pinfunction "GND2_24") (pintype "power_in"))
      (node (ref "U4") (pin "PAD") (pinfunction "PAD_PAD") (pintype "power_in"))
      (node (ref "X1") (pin "6") (pinfunction "VSS_6") (pintype "power_in"))
      (node (ref "X1") (pin "MT1") (pinfunction "GND_MT1") (pintype "power_in"))
      (node (ref "X1") (pin "MT2") (pinfunction "GND1_MT2") (pintype "power_in"))
      (node (ref "X2") (pin "5") (pinfunction "5_5") (pintype "input"))
    )
    (net (code "39") (name "Net-(C32-Pad2)") (class "Default")
      (node (ref "C32") (pin "2") (pinfunction "2_2") (pintype "passive"))
      (node (ref "JP14") (pin "2") (pinfunction "2_2") (pintype "passive"))
    )
    (net (code "40") (name "Net-(IC5-VI)") (class "Default")
      (node (ref "C24") (pin "+") (pinfunction "+_+") (pintype "passive"))
      (node (ref "IC5") (pin "1") (pinfunction "VI_1") (pintype "input"))
      (node (ref "JS16") (pin "1") (pinfunction "1_1") (pintype "passive"))
      (node (ref "R33") (pin "1") (pinfunction "1_1") (pintype "passive"))
    )
    (net (code "41") (name "Net-(IC5-VO)") (class "Default")
      (node (ref "C27") (pin "1") (pinfunction "1_1") (pintype "passive"))
      (node (ref "IC5") (pin "2") (pinfunction "VO_2") (pintype "passive"))
      (node (ref "JP15") (pin "3") (pinfunction "3_3") (pintype "passive"))
    )
    (net (code "42") (name "Net-(IC6-XTAL1)") (class "Default")
      (node (ref "IC6") (pin "8") (pinfunction "XTAL1_8") (pintype "bidirectional"))
      (node (ref "Q1") (pin "3") (pinfunction "3_3") (pintype "passive"))
    )
    (net (code "43") (name "Net-(IC6-XTAL2)") (class "Default")
      (node (ref "IC6") (pin "7") (pinfunction "XTAL2_7") (pintype "bidirectional"))
      (node (ref "Q1") (pin "1") (pinfunction "1_1") (pintype "passive"))
    )
    (net (code "44") (name "Net-(IC7A-O)") (class "Default")
      (node (ref "IC7") (pin "2") (pinfunction "O_2") (pintype "output"))
      (node (ref "X1") (pin "3") (pinfunction "DATA_IN_3") (pintype "input"))
    )
    (net (code "45") (name "Net-(IC7B-O)") (class "Default")
      (node (ref "IC7") (pin "4") (pinfunction "O_4") (pintype "output"))
      (node (ref "X1") (pin "5") (pinfunction "SCLK_5") (pintype "input"))
    )
    (net (code "46") (name "Net-(IC7C-O)") (class "Default")
      (node (ref "IC7") (pin "6") (pinfunction "O_6") (pintype "output"))
      (node (ref "X1") (pin "2") (pinfunction "CS_2") (pintype "input"))
    )
    (net (code "47") (name "Net-(L1-PadC)") (class "Default")
      (node (ref "L1") (pin "C") (pinfunction "C_C") (pintype "passive"))
      (node (ref "R25") (pin "1") (pinfunction "1_1") (pintype "passive"))
    )
    (net (code "48") (name "Net-(M1-D)") (class "Default")
      (node (ref "JP6") (pin "2") (pinfunction "2_2") (pintype "passive"))
      (node (ref "JS1") (pin "2") (pinfunction "2_2") (pintype "passive"))
      (node (ref "M1") (pin "4") (pinfunction "D_4") (pintype "passive"))
    )
    (net (code "49") (name "Net-(M2-D)") (class "Default")
      (node (ref "JP7") (pin "2") (pinfunction "2_2") (pintype "passive"))
      (node (ref "JS2") (pin "2") (pinfunction "2_2") (pintype "passive"))
      (node (ref "M2") (pin "4") (pinfunction "D_4") (pintype "passive"))
    )
    (net (code "50") (name "Net-(M3-D)") (class "Default")
      (node (ref "JP8") (pin "2") (pinfunction "2_2") (pintype "passive"))
      (node (ref "JS3") (pin "2") (pinfunction "2_2") (pintype "passive"))
      (node (ref "M3") (pin "4") (pinfunction "D_4") (pintype "passive"))
    )
    (net (code "51") (name "Net-(R6-E)") (class "Default")
      (node (ref "R17") (pin "1") (pinfunction "1_1") (pintype "passive"))
      (node (ref "R6") (pin "2") (pinfunction "E_2") (pintype "passive"))
    )
    (net (code "52") (name "Net-(R6-S)") (class "Default")
      (node (ref "R6") (pin "W") (pinfunction "S_W") (pintype "passive"))
      (node (ref "U1") (pin "12") (pinfunction "REF_12") (pintype "input"))
    )
    (net (code "53") (name "Net-(R8-E)") (class "Default")
      (node (ref "R35") (pin "1") (pinfunction "1_1") (pintype "passive"))
      (node (ref "R8") (pin "2") (pinfunction "E_2") (pintype "passive"))
    )
    (net (code "54") (name "Net-(R8-S)") (class "Default")
      (node (ref "R8") (pin "W") (pinfunction "S_W") (pintype "passive"))
      (node (ref "U3") (pin "12") (pinfunction "REF_12") (pintype "input"))
    )
    (net (code "55") (name "Net-(R9-E)") (class "Default")
      (node (ref "R38") (pin "1") (pinfunction "1_1") (pintype "passive"))
      (node (ref "R9") (pin "2") (pinfunction "E_2") (pintype "passive"))
    )
    (net (code "56") (name "Net-(R9-S)") (class "Default")
      (node (ref "R9") (pin "W") (pinfunction "S_W") (pintype "passive"))
      (node (ref "U4") (pin "12") (pinfunction "REF_12") (pintype "input"))
    )
    (net (code "57") (name "Net-(R27-E)") (class "Default")
      (node (ref "R27") (pin "2") (pinfunction "E_2") (pintype "passive"))
      (node (ref "R39") (pin "1") (pinfunction "1_1") (pintype "passive"))
    )
    (net (code "58") (name "Net-(R27-S)") (class "Default")
      (node (ref "R27") (pin "W") (pinfunction "S_W") (pintype "passive"))
      (node (ref "U2") (pin "12") (pinfunction "REF_12") (pintype "input"))
    )
    (net (code "59") (name "Net-(U1-CP1)") (class "Default")
      (node (ref "C1") (pin "2") (pinfunction "2_2") (pintype "passive"))
      (node (ref "U1") (pin "1") (pinfunction "CP1_1") (pintype "passive"))
    )
    (net (code "60") (name "Net-(U1-CP2)") (class "Default")
      (node (ref "C1") (pin "1") (pinfunction "1_1") (pintype "passive"))
      (node (ref "U1") (pin "2") (pinfunction "CP2_2") (pintype "passive"))
    )
    (net (code "61") (name "Net-(U1-MS1)") (class "Default")
      (node (ref "MS-X1") (pin "1") (pinfunction "1_1") (pintype "passive"))
      (node (ref "U1") (pin "5") (pinfunction "MS1_5") (pintype "input"))
    )
    (net (code "62") (name "Net-(U1-MS2)") (class "Default")
      (node (ref "MS-X1") (pin "3") (pinfunction "3_3") (pintype "passive"))
      (node (ref "U1") (pin "6") (pinfunction "MS2_6") (pintype "input"))
    )
    (net (code "63") (name "Net-(U1-OUT1A)") (class "Default")
      (node (ref "JP2") (pin "3") (pinfunction "3_3") (pintype "passive"))
      (node (ref "U1") (pin "18") (pinfunction "OUT1A_18") (pintype "output"))
    )
    (net (code "64") (name "Net-(U1-OUT1B)") (class "Default")
      (node (ref "JP2") (pin "4") (pinfunction "4_4") (pintype "passive"))
      (node (ref "U1") (pin "15") (pinfunction "OUT1B_15") (pintype "output"))
    )
    (net (code "65") (name "Net-(U1-OUT2A)") (class "Default")
      (node (ref "JP2") (pin "2") (pinfunction "2_2") (pintype "passive"))
      (node (ref "U1") (pin "19") (pinfunction "OUT2A_19") (pintype "output"))
    )
    (net (code "66") (name "Net-(U1-OUT2B)") (class "Default")
      (node (ref "JP2") (pin "1") (pinfunction "1_1") (pintype "passive"))
      (node (ref "U1") (pin "22") (pinfunction "OUT2B_22") (pintype "output"))
    )
    (net (code "67") (name "Net-(U1-ROSC)") (class "Default")
      (node (ref "R14") (pin "1") (pinfunction "1_1") (pintype "passive"))
      (node (ref "U1") (pin "8") (pinfunction "ROSC_8") (pintype "passive"))
    )
    (net (code "68") (name "Net-(U1-SENSE1)") (class "Default")
      (node (ref "R7") (pin "1") (pinfunction "1_1") (pintype "passive"))
      (node (ref "U1") (pin "17") (pinfunction "SENSE1_17") (pintype "passive"))
    )
    (net (code "69") (name "Net-(U1-SENSE2)") (class "Default")
      (node (ref "R13") (pin "1") (pinfunction "1_1") (pintype "passive"))
      (node (ref "U1") (pin "20") (pinfunction "SENSE2_20") (pintype "passive"))
    )
    (net (code "70") (name "Net-(U1-VCP)") (class "Default")
      (node (ref "C11") (pin "2") (pinfunction "2_2") (pintype "passive"))
      (node (ref "U1") (pin "3") (pinfunction "VCP_3") (pintype "passive"))
    )
    (net (code "71") (name "Net-(U1-VREG)") (class "Default")
      (node (ref "C2") (pin "2") (pinfunction "2_2") (pintype "passive"))
      (node (ref "U1") (pin "4") (pinfunction "VREG_4") (pintype "passive"))
    )
    (net (code "72") (name "Net-(U1-~{RESET})") (class "Default")
      (node (ref "R16") (pin "2") (pinfunction "2_2") (pintype "passive"))
      (node (ref "U1") (pin "7") (pinfunction "~{RESET}_7") (pintype "input"))
      (node (ref "U1") (pin "9") (pinfunction "~{SLEEP}_9") (pintype "input"))
    )
    (net (code "73") (name "Net-(U2-CP1)") (class "Default")
      (node (ref "C46") (pin "2") (pinfunction "2_2") (pintype "passive"))
      (node (ref "U2") (pin "1") (pinfunction "CP1_1") (pintype "passive"))
    )
    (net (code "74") (name "Net-(U2-CP2)") (class "Default")
      (node (ref "C46") (pin "1") (pinfunction "1_1") (pintype "passive"))
      (node (ref "U2") (pin "2") (pinfunction "CP2_2") (pintype "passive"))
    )
    (net (code "75") (name "Net-(U2-MS1)") (class "Default")
      (node (ref "MS-X") (pin "1") (pinfunction "1_1") (pintype "passive"))
      (node (ref "U2") (pin "5") (pinfunction "MS1_5") (pintype "input"))
    )
    (net (code "76") (name "Net-(U2-MS2)") (class "Default")
      (node (ref "MS-X") (pin "3") (pinfunction "3_3") (pintype "passive"))
      (node (ref "U2") (pin "6") (pinfunction "MS2_6") (pintype "input"))
    )
    (net (code "77") (name "Net-(U2-OUT1A)") (class "Default")
      (node (ref "JP1") (pin "3") (pinfunction "3_3") (pintype "passive"))
      (node (ref "U2") (pin "18") (pinfunction "OUT1A_18") (pintype "output"))
    )
    (net (code "78") (name "Net-(U2-OUT1B)") (class "Default")
      (node (ref "JP1") (pin "4") (pinfunction "4_4") (pintype "passive"))
      (node (ref "U2") (pin "15") (pinfunction "OUT1B_15") (pintype "output"))
    )
    (net (code "79") (name "Net-(U2-OUT2A)") (class "Default")
      (node (ref "JP1") (pin "2") (pinfunction "2_2") (pintype "passive"))
      (node (ref "U2") (pin "19") (pinfunction "OUT2A_19") (pintype "output"))
    )
    (net (code "80") (name "Net-(U2-OUT2B)") (class "Default")
      (node (ref "JP1") (pin "1") (pinfunction "1_1") (pintype "passive"))
      (node (ref "U2") (pin "22") (pinfunction "OUT2B_22") (pintype "output"))
    )
    (net (code "81") (name "Net-(U2-ROSC)") (class "Default")
      (node (ref "R30") (pin "1") (pinfunction "1_1") (pintype "passive"))
      (node (ref "U2") (pin "8") (pinfunction "ROSC_8") (pintype "passive"))
    )
    (net (code "82") (name "Net-(U2-SENSE1)") (class "Default")
      (node (ref "R28") (pin "1") (pinfunction "1_1") (pintype "passive"))
      (node (ref "U2") (pin "17") (pinfunction "SENSE1_17") (pintype "passive"))
    )
    (net (code "83") (name "Net-(U2-SENSE2)") (class "Default")
      (node (ref "R29") (pin "1") (pinfunction "1_1") (pintype "passive"))
      (node (ref "U2") (pin "20") (pinfunction "SENSE2_20") (pintype "passive"))
    )
    (net (code "84") (name "Net-(U2-VCP)") (class "Default")
      (node (ref "C49") (pin "2") (pinfunction "2_2") (pintype "passive"))
      (node (ref "U2") (pin "3") (pinfunction "VCP_3") (pintype "passive"))
    )
    (net (code "85") (name "Net-(U2-VREG)") (class "Default")
      (node (ref "C47") (pin "2") (pinfunction "2_2") (pintype "passive"))
      (node (ref "U2") (pin "4") (pinfunction "VREG_4") (pintype "passive"))
    )
    (net (code "86") (name "Net-(U2-~{RESET})") (class "Default")
      (node (ref "R32") (pin "2") (pinfunction "2_2") (pintype "passive"))
      (node (ref "U2") (pin "7") (pinfunction "~{RESET}_7") (pintype "input"))
      (node (ref "U2") (pin "9") (pinfunction "~{SLEEP}_9") (pintype "input"))
    )
    (net (code "87") (name "Net-(U3-CP1)") (class "Default")
      (node (ref "C3") (pin "2") (pinfunction "2_2") (pintype "passive"))
      (node (ref "U3") (pin "1") (pinfunction "CP1_1") (pintype "passive"))
    )
    (net (code "88") (name "Net-(U3-CP2)") (class "Default")
      (node (ref "C3") (pin "1") (pinfunction "1_1") (pintype "passive"))
      (node (ref "U3") (pin "2") (pinfunction "CP2_2") (pintype "passive"))
    )
    (net (code "89") (name "Net-(U3-MS1)") (class "Default")
      (node (ref "MS-X2") (pin "1") (pinfunction "1_1") (pintype "passive"))
      (node (ref "U3") (pin "5") (pinfunction "MS1_5") (pintype "input"))
    )
    (net (code "90") (name "Net-(U3-MS2)") (class "Default")
      (node (ref "MS-X2") (pin "3") (pinfunction "3_3") (pintype "passive"))
      (node (ref "U3") (pin "6") (pinfunction "MS2_6") (pintype "input"))
    )
    (net (code "91") (name "Net-(U3-OUT1A)") (class "Default")
      (node (ref "JP3") (pin "3") (pinfunction "3_3") (pintype "passive"))
      (node (ref "U3") (pin "18") (pinfunction "OUT1A_18") (pintype "output"))
    )
    (net (code "92") (name "Net-(U3-OUT1B)") (class "Default")
      (node (ref "JP3") (pin "4") (pinfunction "4_4") (pintype "passive"))
      (node (ref "U3") (pin "15") (pinfunction "OUT1B_15") (pintype "output"))
    )
    (net (code "93") (name "Net-(U3-OUT2A)") (class "Default")
      (node (ref "JP3") (pin "2") (pinfunction "2_2") (pintype "passive"))
      (node (ref "U3") (pin "19") (pinfunction "OUT2A_19") (pintype "output"))
    )
    (net (code "94") (name "Net-(U3-OUT2B)") (class "Default")
      (node (ref "JP3") (pin "1") (pinfunction "1_1") (pintype "passive"))
      (node (ref "U3") (pin "22") (pinfunction "OUT2B_22") (pintype "output"))
    )
    (net (code "95") (name "Net-(U3-ROSC)") (class "Default")
      (node (ref "R20") (pin "1") (pinfunction "1_1") (pintype "passive"))
      (node (ref "U3") (pin "8") (pinfunction "ROSC_8") (pintype "passive"))
    )
    (net (code "96") (name "Net-(U3-SENSE1)") (class "Default")
      (node (ref "R18") (pin "1") (pinfunction "1_1") (pintype "passive"))
      (node (ref "U3") (pin "17") (pinfunction "SENSE1_17") (pintype "passive"))
    )
    (net (code "97") (name "Net-(U3-SENSE2)") (class "Default")
      (node (ref "R19") (pin "1") (pinfunction "1_1") (pintype "passive"))
      (node (ref "U3") (pin "20") (pinfunction "SENSE2_20") (pintype "passive"))
    )
    (net (code "98") (name "Net-(U3-VCP)") (class "Default")
      (node (ref "C16") (pin "2") (pinfunction "2_2") (pintype "passive"))
      (node (ref "U3") (pin "3") (pinfunction "VCP_3") (pintype "passive"))
    )
    (net (code "99") (name "Net-(U3-VREG)") (class "Default")
      (node (ref "C14") (pin "2") (pinfunction "2_2") (pintype "passive"))
      (node (ref "U3") (pin "4") (pinfunction "VREG_4") (pintype "passive"))
    )
    (net (code "100") (name "Net-(U3-~{RESET})") (class "Default")
      (node (ref "R34") (pin "2") (pinfunction "2_2") (pintype "passive"))
      (node (ref "U3") (pin "7") (pinfunction "~{RESET}_7") (pintype "input"))
      (node (ref "U3") (pin "9") (pinfunction "~{SLEEP}_9") (pintype "input"))
    )
    (net (code "101") (name "Net-(U4-CP1)") (class "Default")
      (node (ref "C4") (pin "2") (pinfunction "2_2") (pintype "passive"))
      (node (ref "U4") (pin "1") (pinfunction "CP1_1") (pintype "passive"))
    )
    (net (code "102") (name "Net-(U4-CP2)") (class "Default")
      (node (ref "C4") (pin "1") (pinfunction "1_1") (pintype "passive"))
      (node (ref "U4") (pin "2") (pinfunction "CP2_2") (pintype "passive"))
    )
    (net (code "103") (name "Net-(U4-MS1)") (class "Default")
      (node (ref "MS-X3") (pin "1") (pinfunction "1_1") (pintype "passive"))
      (node (ref "U4") (pin "5") (pinfunction "MS1_5") (pintype "input"))
    )
    (net (code "104") (name "Net-(U4-MS2)") (class "Default")
      (node (ref "MS-X3") (pin "3") (pinfunction "3_3") (pintype "passive"))
      (node (ref "U4") (pin "6") (pinfunction "MS2_6") (pintype "input"))
    )
    (net (code "105") (name "Net-(U4-OUT1A)") (class "Default")
      (node (ref "JP4") (pin "3") (pinfunction "3_3") (pintype "passive"))
      (node (ref "U4") (pin "18") (pinfunction "OUT1A_18") (pintype "output"))
    )
    (net (code "106") (name "Net-(U4-OUT1B)") (class "Default")
      (node (ref "JP4") (pin "4") (pinfunction "4_4") (pintype "passive"))
      (node (ref "U4") (pin "15") (pinfunction "OUT1B_15") (pintype "output"))
    )
    (net (code "107") (name "Net-(U4-OUT2A)") (class "Default")
      (node (ref "JP4") (pin "2") (pinfunction "2_2") (pintype "passive"))
      (node (ref "U4") (pin "19") (pinfunction "OUT2A_19") (pintype "output"))
    )
    (net (code "108") (name "Net-(U4-OUT2B)") (class "Default")
      (node (ref "JP4") (pin "1") (pinfunction "1_1") (pintype "passive"))
      (node (ref "U4") (pin "22") (pinfunction "OUT2B_22") (pintype "output"))
    )
    (net (code "109") (name "Net-(U4-ROSC)") (class "Default")
      (node (ref "R24") (pin "1") (pinfunction "1_1") (pintype "passive"))
      (node (ref "U4") (pin "8") (pinfunction "ROSC_8") (pintype "passive"))
    )
    (net (code "110") (name "Net-(U4-SENSE1)") (class "Default")
      (node (ref "R22") (pin "1") (pinfunction "1_1") (pintype "passive"))
      (node (ref "U4") (pin "17") (pinfunction "SENSE1_17") (pintype "passive"))
    )
    (net (code "111") (name "Net-(U4-SENSE2)") (class "Default")
      (node (ref "R23") (pin "1") (pinfunction "1_1") (pintype "passive"))
      (node (ref "U4") (pin "20") (pinfunction "SENSE2_20") (pintype "passive"))
    )
    (net (code "112") (name "Net-(U4-VCP)") (class "Default")
      (node (ref "C21") (pin "2") (pinfunction "2_2") (pintype "passive"))
      (node (ref "U4") (pin "3") (pinfunction "VCP_3") (pintype "passive"))
    )
    (net (code "113") (name "Net-(U4-VREG)") (class "Default")
      (node (ref "C19") (pin "2") (pinfunction "2_2") (pintype "passive"))
      (node (ref "U4") (pin "4") (pinfunction "VREG_4") (pintype "passive"))
    )
    (net (code "114") (name "Net-(U4-~{RESET})") (class "Default")
      (node (ref "R37") (pin "2") (pinfunction "2_2") (pintype "passive"))
      (node (ref "U4") (pin "7") (pinfunction "~{RESET}_7") (pintype "input"))
      (node (ref "U4") (pin "9") (pinfunction "~{SLEEP}_9") (pintype "input"))
    )
    (net (code "115") (name "VCC") (class "Default")
      (node (ref "C10") (pin "2") (pinfunction "2_2") (pintype "passive"))
      (node (ref "C15") (pin "2") (pinfunction "2_2") (pintype "passive"))
      (node (ref "C20") (pin "2") (pinfunction "2_2") (pintype "passive"))
      (node (ref "C41") (pin "1") (pinfunction "1_1") (pintype "passive"))
      (node (ref "C42") (pin "1") (pinfunction "1_1") (pintype "passive"))
      (node (ref "C43") (pin "2") (pinfunction "2_2") (pintype "passive"))
      (node (ref "C44") (pin "1") (pinfunction "1_1") (pintype "passive"))
      (node (ref "C45") (pin "2") (pinfunction "2_2") (pintype "passive"))
      (node (ref "C48") (pin "2") (pinfunction "2_2") (pintype "passive"))
      (node (ref "IC6") (pin "17") (pinfunction "VCC_17") (pintype "power_in"))
      (node (ref "IC6") (pin "27") (pinfunction "AVCC_27") (pintype "power_in"))
      (node (ref "IC6") (pin "29") (pinfunction "AREF_29") (pintype "passive"))
      (node (ref "IC6") (pin "38") (pinfunction "VCC_38") (pintype "power_in"))
      (node (ref "IC6") (pin "5") (pinfunction "VCC_5") (pintype "power_in"))
      (node (ref "IC8") (pin "20") (pinfunction "VCC_20") (pintype "power_in"))
      (node (ref "IC8") (pin "4") (pinfunction "VCCIO_4") (pintype "power_in"))
      (node (ref "JP15") (pin "2") (pinfunction "2_2") (pintype "passive"))
      (node (ref "JP16") (pin "9") (pinfunction "9_9") (pintype "passive"))
      (node (ref "JP17") (pin "2") (pinfunction "2_2") (pintype "passive"))
      (node (ref "MS-X") (pin "2") (pinfunction "2_2") (pintype "passive"))
      (node (ref "MS-X1") (pin "2") (pinfunction "2_2") (pintype "passive"))
      (node (ref "MS-X2") (pin "2") (pinfunction "2_2") (pintype "passive"))
      (node (ref "MS-X3") (pin "2") (pinfunction "2_2") (pintype "passive"))
      (node (ref "R1") (pin "1") (pinfunction "1_1") (pintype "passive"))
      (node (ref "R15") (pin "1") (pinfunction "1_1") (pintype "passive"))
      (node (ref "R16") (pin "1") (pinfunction "1_1") (pintype "passive"))
      (node (ref "R17") (pin "2") (pinfunction "2_2") (pintype "passive"))
      (node (ref "R2") (pin "1") (pinfunction "1_1") (pintype "passive"))
      (node (ref "R21") (pin "1") (pinfunction "1_1") (pintype "passive"))
      (node (ref "R26") (pin "2") (pinfunction "2_2") (pintype "passive"))
      (node (ref "R3") (pin "1") (pinfunction "1_1") (pintype "passive"))
      (node (ref "R31") (pin "1") (pinfunction "1_1") (pintype "passive"))
      (node (ref "R32") (pin "1") (pinfunction "1_1") (pintype "passive"))
      (node (ref "R34") (pin "1") (pinfunction "1_1") (pintype "passive"))
      (node (ref "R35") (pin "2") (pinfunction "2_2") (pintype "passive"))
      (node (ref "R36") (pin "1") (pinfunction "1_1") (pintype "passive"))
      (node (ref "R37") (pin "1") (pinfunction "1_1") (pintype "passive"))
      (node (ref "R38") (pin "2") (pinfunction "2_2") (pintype "passive"))
      (node (ref "R39") (pin "2") (pinfunction "2_2") (pintype "passive"))
      (node (ref "R4") (pin "1") (pinfunction "1_1") (pintype "passive"))
      (node (ref "R5") (pin "1") (pinfunction "1_1") (pintype "passive"))
      (node (ref "U1") (pin "10") (pinfunction "VDD_10") (pintype "power_in"))
      (node (ref "U2") (pin "10") (pinfunction "VDD_10") (pintype "power_in"))
      (node (ref "U3") (pin "10") (pinfunction "VDD_10") (pintype "power_in"))
      (node (ref "U4") (pin "10") (pinfunction "VDD_10") (pintype "power_in"))
    )
    (net (code "116") (name "VDD") (class "Default")
      (node (ref "C31") (pin "2") (pinfunction "2_2") (pintype "passive"))
      (node (ref "IC7") (pin "1") (pinfunction "VDD_1") (pintype "power_in"))
      (node (ref "IC8") (pin "17") (pinfunction "3V3OUT_17") (pintype "output"))
      (node (ref "X1") (pin "4") (pinfunction "VDD_4") (pintype "power_in"))
    )
    (net (code "117") (name "VMOT") (class "Default")
      (node (ref "C11") (pin "1") (pinfunction "1_1") (pintype "passive"))
      (node (ref "C12") (pin "+") (pinfunction "+_+") (pintype "passive"))
      (node (ref "C13") (pin "1") (pinfunction "1_1") (pintype "passive"))
      (node (ref "C16") (pin "1") (pinfunction "1_1") (pintype "passive"))
      (node (ref "C17") (pin "+") (pinfunction "+_+") (pintype "passive"))
      (node (ref "C18") (pin "1") (pinfunction "1_1") (pintype "passive"))
      (node (ref "C21") (pin "1") (pinfunction "1_1") (pintype "passive"))
      (node (ref "C22") (pin "+") (pinfunction "+_+") (pintype "passive"))
      (node (ref "C23") (pin "1") (pinfunction "1_1") (pintype "passive"))
      (node (ref "C28") (pin "+") (pinfunction "+_+") (pintype "passive"))
      (node (ref "C29") (pin "+") (pinfunction "+_+") (pintype "passive"))
      (node (ref "C30") (pin "+") (pinfunction "+_+") (pintype "passive"))
      (node (ref "C49") (pin "1") (pinfunction "1_1") (pintype "passive"))
      (node (ref "C50") (pin "+") (pinfunction "+_+") (pintype "passive"))
      (node (ref "C51") (pin "1") (pinfunction "1_1") (pintype "passive"))
      (node (ref "JP5") (pin "1") (pinfunction "1_1") (pintype "passive"))
      (node (ref "JP6") (pin "1") (pinfunction "1_1") (pintype "passive"))
      (node (ref "JP7") (pin "1") (pinfunction "1_1") (pintype "passive"))
      (node (ref "JP8") (pin "1") (pinfunction "1_1") (pintype "passive"))
      (node (ref "JS16") (pin "2") (pinfunction "2_2") (pintype "passive"))
      (node (ref "R33") (pin "2") (pinfunction "2_2") (pintype "passive"))
      (node (ref "U1") (pin "16") (pinfunction "VBB1_16") (pintype "power_in"))
      (node (ref "U1") (pin "21") (pinfunction "VBB2_21") (pintype "power_in"))
      (node (ref "U2") (pin "16") (pinfunction "VBB1_16") (pintype "power_in"))
      (node (ref "U2") (pin "21") (pinfunction "VBB2_21") (pintype "power_in"))
      (node (ref "U3") (pin "16") (pinfunction "VBB1_16") (pintype "power_in"))
      (node (ref "U3") (pin "21") (pinfunction "VBB2_21") (pintype "power_in"))
      (node (ref "U4") (pin "16") (pinfunction "VBB1_16") (pintype "power_in"))
      (node (ref "U4") (pin "21") (pinfunction "VBB2_21") (pintype "power_in"))
    )
    (net (code "118") (name "unconnected-(IC8-CTS-Pad11)") (class "Default")
      (node (ref "IC8") (pin "11") (pinfunction "CTS_11") (pintype "bidirectional"))
    )
    (net (code "119") (name "unconnected-(IC8-RTS-Pad3)") (class "Default")
      (node (ref "IC8") (pin "3") (pinfunction "RTS_3") (pintype "bidirectional"))
    )
    (net (code "120") (name "unconnected-(IC8-RXLED-Pad22)") (class "Default")
      (node (ref "IC8") (pin "22") (pinfunction "RXLED_22") (pintype "bidirectional"))
    )
    (net (code "121") (name "unconnected-(IC8-TXLED-Pad23)") (class "Default")
      (node (ref "IC8") (pin "23") (pinfunction "TXLED_23") (pintype "bidirectional"))
    )
    (net (code "122") (name "unconnected-(X1-CARD_DETECT-PadCD1)") (class "Default")
      (node (ref "X1") (pin "CD1") (pinfunction "CARD_DETECT_CD1") (pintype "passive"))
    )
    (net (code "123") (name "unconnected-(X1-CARD_DETECT1-PadCD2)") (class "Default")
      (node (ref "X1") (pin "CD2") (pinfunction "CARD_DETECT1_CD2") (pintype "passive"))
    )
    (net (code "124") (name "unconnected-(X1-DAT1-Pad8)") (class "Default")
      (node (ref "X1") (pin "8") (pinfunction "DAT1_8") (pintype "bidirectional"))
    )
    (net (code "125") (name "unconnected-(X1-DAT2-Pad1)") (class "Default")
      (node (ref "X1") (pin "1") (pinfunction "DAT2_1") (pintype "bidirectional"))
    )
    (net (code "126") (name "unconnected-(X2-Pad4)") (class "Default")
      (node (ref "X2") (pin "4") (pinfunction "4_4") (pintype "input"))
    )
  )
)
